# Condor2a_Pin_REV_C.net
KiCad netlist of a schematic drawn in Altium Designer
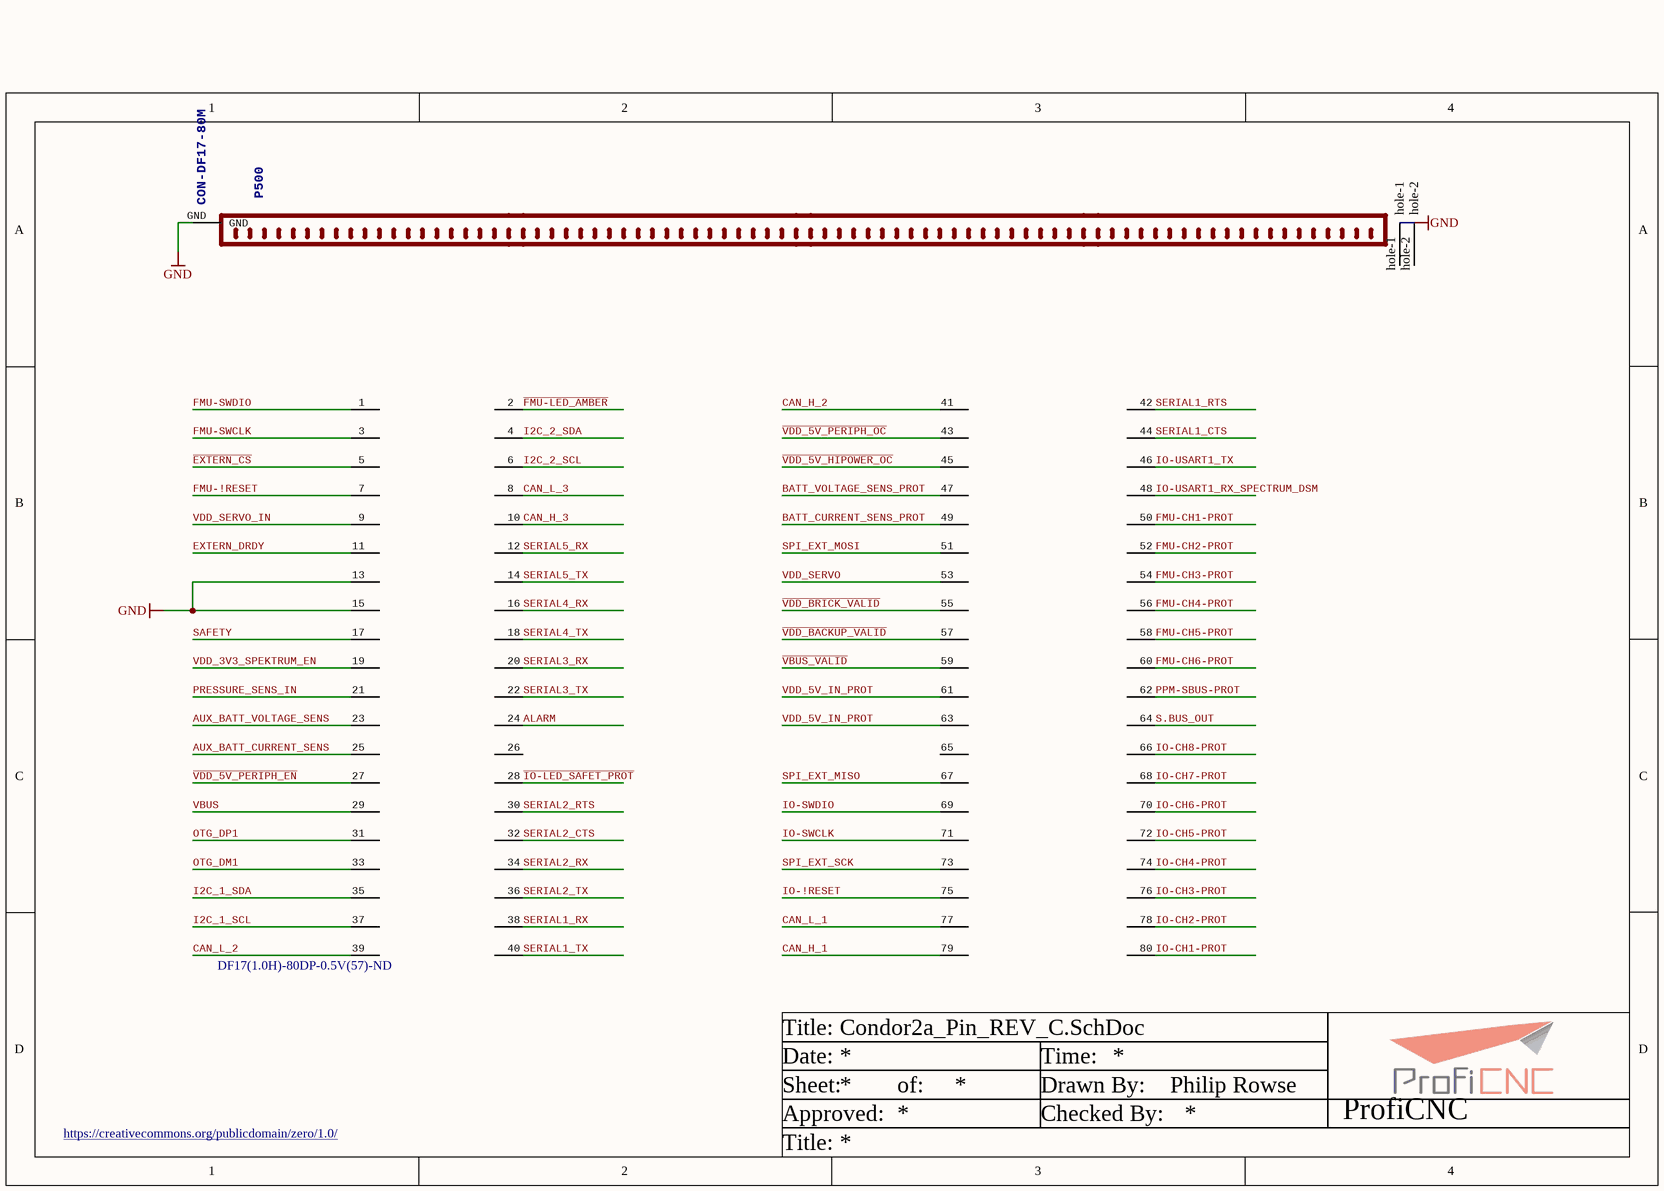
[diagram p0: Condor2a_Pin_REV_C.SchDoc]

(export (version "E")
  (design (tool "Eeschema 10.0.6"))
  (components
    (comp (ref "P500")
      (value "CON-DF17-80M")
      (footprint "CON-DF17-80M")
      (description "Connector, Header, 80Pos, .5MM, DUAL, SMD, Au")
      (fields (field (name "SUPPLIER PART NUMBER 1") "DF17(1.0H)-80DP-0.5V(57)-ND"))
      (libsource (lib "CB_REV_C") (part "CON-DF17-80M"))
    )
  )
  (nets
    (net (code "1") (name "/ALARM") (class "Default")
      (node (ref "P500") (pin "24") (pinfunction "24_24") (pintype "passive"))
    )
    (net (code "2") (name "/AUX_BATT_CURRENT_SENS") (class "Default")
      (node (ref "P500") (pin "25") (pinfunction "25_25") (pintype "passive"))
    )
    (net (code "3") (name "/AUX_BATT_VOLTAGE_SENS") (class "Default")
      (node (ref "P500") (pin "23") (pinfunction "23_23") (pintype "passive"))
    )
    (net (code "4") (name "/BATT_CURRENT_SENS_PROT") (class "Default")
      (node (ref "P500") (pin "49") (pinfunction "49_49") (pintype "passive"))
    )
    (net (code "5") (name "/BATT_VOLTAGE_SENS_PROT") (class "Default")
      (node (ref "P500") (pin "47") (pinfunction "47_47") (pintype "passive"))
    )
    (net (code "6") (name "/CAN_H_1") (class "Default")
      (node (ref "P500") (pin "79") (pinfunction "79_79") (pintype "passive"))
    )
    (net (code "7") (name "/CAN_H_2") (class "Default")
      (node (ref "P500") (pin "41") (pinfunction "41_41") (pintype "passive"))
    )
    (net (code "8") (name "/CAN_H_3") (class "Default")
      (node (ref "P500") (pin "10") (pinfunction "10_10") (pintype "passive"))
    )
    (net (code "9") (name "/CAN_L_1") (class "Default")
      (node (ref "P500") (pin "77") (pinfunction "77_77") (pintype "passive"))
    )
    (net (code "10") (name "/CAN_L_2") (class "Default")
      (node (ref "P500") (pin "39") (pinfunction "39_39") (pintype "passive"))
    )
    (net (code "11") (name "/CAN_L_3") (class "Default")
      (node (ref "P500") (pin "8") (pinfunction "8_8") (pintype "passive"))
    )
    (net (code "12") (name "/EXTERN_DRDY") (class "Default")
      (node (ref "P500") (pin "11") (pinfunction "11_11") (pintype "passive"))
    )
    (net (code "13") (name "/FMU-!RESET") (class "Default")
      (node (ref "P500") (pin "7") (pinfunction "7_7") (pintype "passive"))
    )
    (net (code "14") (name "/FMU-CH1-PROT") (class "Default")
      (node (ref "P500") (pin "50") (pinfunction "50_50") (pintype "passive"))
    )
    (net (code "15") (name "/FMU-CH2-PROT") (class "Default")
      (node (ref "P500") (pin "52") (pinfunction "52_52") (pintype "passive"))
    )
    (net (code "16") (name "/FMU-CH3-PROT") (class "Default")
      (node (ref "P500") (pin "54") (pinfunction "54_54") (pintype "passive"))
    )
    (net (code "17") (name "/FMU-CH4-PROT") (class "Default")
      (node (ref "P500") (pin "56") (pinfunction "56_56") (pintype "passive"))
    )
    (net (code "18") (name "/FMU-CH5-PROT") (class "Default")
      (node (ref "P500") (pin "58") (pinfunction "58_58") (pintype "passive"))
    )
    (net (code "19") (name "/FMU-CH6-PROT") (class "Default")
      (node (ref "P500") (pin "60") (pinfunction "60_60") (pintype "passive"))
    )
    (net (code "20") (name "/FMU-SWCLK") (class "Default")
      (node (ref "P500") (pin "3") (pinfunction "3_3") (pintype "passive"))
    )
    (net (code "21") (name "/FMU-SWDIO") (class "Default")
      (node (ref "P500") (pin "1") (pinfunction "1_1") (pintype "passive"))
    )
    (net (code "22") (name "/I2C_1_SCL") (class "Default")
      (node (ref "P500") (pin "37") (pinfunction "37_37") (pintype "passive"))
    )
    (net (code "23") (name "/I2C_1_SDA") (class "Default")
      (node (ref "P500") (pin "35") (pinfunction "35_35") (pintype "passive"))
    )
    (net (code "24") (name "/I2C_2_SCL") (class "Default")
      (node (ref "P500") (pin "6") (pinfunction "6_6") (pintype "passive"))
    )
    (net (code "25") (name "/I2C_2_SDA") (class "Default")
      (node (ref "P500") (pin "4") (pinfunction "4_4") (pintype "passive"))
    )
    (net (code "26") (name "/IO-!RESET") (class "Default")
      (node (ref "P500") (pin "75") (pinfunction "75_75") (pintype "passive"))
    )
    (net (code "27") (name "/IO-CH1-PROT") (class "Default")
      (node (ref "P500") (pin "80") (pinfunction "80_80") (pintype "passive"))
    )
    (net (code "28") (name "/IO-CH2-PROT") (class "Default")
      (node (ref "P500") (pin "78") (pinfunction "78_78") (pintype "passive"))
    )
    (net (code "29") (name "/IO-CH3-PROT") (class "Default")
      (node (ref "P500") (pin "76") (pinfunction "76_76") (pintype "passive"))
    )
    (net (code "30") (name "/IO-CH4-PROT") (class "Default")
      (node (ref "P500") (pin "74") (pinfunction "74_74") (pintype "passive"))
    )
    (net (code "31") (name "/IO-CH5-PROT") (class "Default")
      (node (ref "P500") (pin "72") (pinfunction "72_72") (pintype "passive"))
    )
    (net (code "32") (name "/IO-CH6-PROT") (class "Default")
      (node (ref "P500") (pin "70") (pinfunction "70_70") (pintype "passive"))
    )
    (net (code "33") (name "/IO-CH7-PROT") (class "Default")
      (node (ref "P500") (pin "68") (pinfunction "68_68") (pintype "passive"))
    )
    (net (code "34") (name "/IO-CH8-PROT") (class "Default")
      (node (ref "P500") (pin "66") (pinfunction "66_66") (pintype "passive"))
    )
    (net (code "35") (name "/IO-SWCLK") (class "Default")
      (node (ref "P500") (pin "71") (pinfunction "71_71") (pintype "passive"))
    )
    (net (code "36") (name "/IO-SWDIO") (class "Default")
      (node (ref "P500") (pin "69") (pinfunction "69_69") (pintype "passive"))
    )
    (net (code "37") (name "/IO-USART1_RX_SPECTRUM_DSM") (class "Default")
      (node (ref "P500") (pin "48") (pinfunction "48_48") (pintype "passive"))
    )
    (net (code "38") (name "/IO-USART1_TX") (class "Default")
      (node (ref "P500") (pin "46") (pinfunction "46_46") (pintype "passive"))
    )
    (net (code "39") (name "/OTG_DM1") (class "Default")
      (node (ref "P500") (pin "33") (pinfunction "33_33") (pintype "passive"))
    )
    (net (code "40") (name "/OTG_DP1") (class "Default")
      (node (ref "P500") (pin "31") (pinfunction "31_31") (pintype "passive"))
    )
    (net (code "41") (name "/PPM-SBUS-PROT") (class "Default")
      (node (ref "P500") (pin "62") (pinfunction "62_62") (pintype "passive"))
    )
    (net (code "42") (name "/PRESSURE_SENS_IN") (class "Default")
      (node (ref "P500") (pin "21") (pinfunction "21_21") (pintype "passive"))
    )
    (net (code "43") (name "/S.BUS_OUT") (class "Default")
      (node (ref "P500") (pin "64") (pinfunction "64_64") (pintype "passive"))
    )
    (net (code "44") (name "/SAFETY") (class "Default")
      (node (ref "P500") (pin "17") (pinfunction "17_17") (pintype "passive"))
    )
    (net (code "45") (name "/SERIAL1_CTS") (class "Default")
      (node (ref "P500") (pin "44") (pinfunction "44_44") (pintype "passive"))
    )
    (net (code "46") (name "/SERIAL1_RTS") (class "Default")
      (node (ref "P500") (pin "42") (pinfunction "42_42") (pintype "passive"))
    )
    (net (code "47") (name "/SERIAL1_RX") (class "Default")
      (node (ref "P500") (pin "38") (pinfunction "38_38") (pintype "passive"))
    )
    (net (code "48") (name "/SERIAL1_TX") (class "Default")
      (node (ref "P500") (pin "40") (pinfunction "40_40") (pintype "passive"))
    )
    (net (code "49") (name "/SERIAL2_CTS") (class "Default")
      (node (ref "P500") (pin "32") (pinfunction "32_32") (pintype "passive"))
    )
    (net (code "50") (name "/SERIAL2_RTS") (class "Default")
      (node (ref "P500") (pin "30") (pinfunction "30_30") (pintype "passive"))
    )
    (net (code "51") (name "/SERIAL2_RX") (class "Default")
      (node (ref "P500") (pin "34") (pinfunction "34_34") (pintype "passive"))
    )
    (net (code "52") (name "/SERIAL2_TX") (class "Default")
      (node (ref "P500") (pin "36") (pinfunction "36_36") (pintype "passive"))
    )
    (net (code "53") (name "/SERIAL3_RX") (class "Default")
      (node (ref "P500") (pin "20") (pinfunction "20_20") (pintype "passive"))
    )
    (net (code "54") (name "/SERIAL3_TX") (class "Default")
      (node (ref "P500") (pin "22") (pinfunction "22_22") (pintype "passive"))
    )
    (net (code "55") (name "/SERIAL4_RX") (class "Default")
      (node (ref "P500") (pin "16") (pinfunction "16_16") (pintype "passive"))
    )
    (net (code "56") (name "/SERIAL4_TX") (class "Default")
      (node (ref "P500") (pin "18") (pinfunction "18_18") (pintype "passive"))
    )
    (net (code "57") (name "/SERIAL5_RX") (class "Default")
      (node (ref "P500") (pin "12") (pinfunction "12_12") (pintype "passive"))
    )
    (net (code "58") (name "/SERIAL5_TX") (class "Default")
      (node (ref "P500") (pin "14") (pinfunction "14_14") (pintype "passive"))
    )
    (net (code "59") (name "/SPI_EXT_MISO") (class "Default")
      (node (ref "P500") (pin "67") (pinfunction "67_67") (pintype "passive"))
    )
    (net (code "60") (name "/SPI_EXT_MOSI") (class "Default")
      (node (ref "P500") (pin "51") (pinfunction "51_51") (pintype "passive"))
    )
    (net (code "61") (name "/SPI_EXT_SCK") (class "Default")
      (node (ref "P500") (pin "73") (pinfunction "73_73") (pintype "passive"))
    )
    (net (code "62") (name "/VBUS") (class "Default")
      (node (ref "P500") (pin "29") (pinfunction "29_29") (pintype "passive"))
    )
    (net (code "63") (name "/VDD_3V3_SPEKTRUM_EN") (class "Default")
      (node (ref "P500") (pin "19") (pinfunction "19_19") (pintype "passive"))
    )
    (net (code "64") (name "/VDD_5V_IN_PROT") (class "Default")
      (node (ref "P500") (pin "61") (pinfunction "61_61") (pintype "passive"))
      (node (ref "P500") (pin "63") (pinfunction "63_63") (pintype "passive"))
    )
    (net (code "65") (name "/VDD_SERVO") (class "Default")
      (node (ref "P500") (pin "53") (pinfunction "53_53") (pintype "passive"))
    )
    (net (code "66") (name "/VDD_SERVO_IN") (class "Default")
      (node (ref "P500") (pin "9") (pinfunction "9_9") (pintype "passive"))
    )
    (net (code "67") (name "/~{EXTERN_CS}") (class "Default")
      (node (ref "P500") (pin "5") (pinfunction "5_5") (pintype "passive"))
    )
    (net (code "68") (name "/~{FMU-LED_AMBER}") (class "Default")
      (node (ref "P500") (pin "2") (pinfunction "2_2") (pintype "passive"))
    )
    (net (code "69") (name "/~{IO-LED_SAFET_PROT}") (class "Default")
      (node (ref "P500") (pin "28") (pinfunction "28_28") (pintype "passive"))
    )
    (net (code "70") (name "/~{VBUS_VALID}") (class "Default")
      (node (ref "P500") (pin "59") (pinfunction "59_59") (pintype "passive"))
    )
    (net (code "71") (name "/~{VDD_5V_HIPOWER_OC}") (class "Default")
      (node (ref "P500") (pin "45") (pinfunction "45_45") (pintype "passive"))
    )
    (net (code "72") (name "/~{VDD_5V_PERIPH_EN}") (class "Default")
      (node (ref "P500") (pin "27") (pinfunction "27_27") (pintype "passive"))
    )
    (net (code "73") (name "/~{VDD_5V_PERIPH_OC}") (class "Default")
      (node (ref "P500") (pin "43") (pinfunction "43_43") (pintype "passive"))
    )
    (net (code "74") (name "/~{VDD_BACKUP_VALID}") (class "Default")
      (node (ref "P500") (pin "57") (pinfunction "57_57") (pintype "passive"))
    )
    (net (code "75") (name "/~{VDD_BRICK_VALID}") (class "Default")
      (node (ref "P500") (pin "55") (pinfunction "55_55") (pintype "passive"))
    )
    (net (code "76") (name "GND") (class "Default")
      (node (ref "P500") (pin "13") (pinfunction "13_13") (pintype "passive"))
      (node (ref "P500") (pin "15") (pinfunction "15_15") (pintype "passive"))
      (node (ref "P500") (pin "GND") (pinfunction "GND_GND") (pintype "passive"))
    )
    (net (code "77") (name "unconnected-(P500-Pad26)") (class "Default")
      (node (ref "P500") (pin "26") (pinfunction "26_26") (pintype "passive"))
    )
    (net (code "78") (name "unconnected-(P500-Pad65)") (class "Default")
      (node (ref "P500") (pin "65") (pinfunction "65_65") (pintype "passive"))
    )
    (net (code "79") (name "unconnected-(P500-Padhole-1)") (class "Default")
      (node (ref "P500") (pin "hole-1") (pinfunction "hole-1_hole-1") (pintype "passive"))
    )
    (net (code "80") (name "unconnected-(P500-Padhole-2)") (class "Default")
      (node (ref "P500") (pin "hole-2") (pinfunction "hole-2_hole-2") (pintype "passive"))
    )
  )
)
